# SCH_Eagle-Blinkyy_2025-12-08.net
KiCad netlist of a schematic drawn in EasyEDA
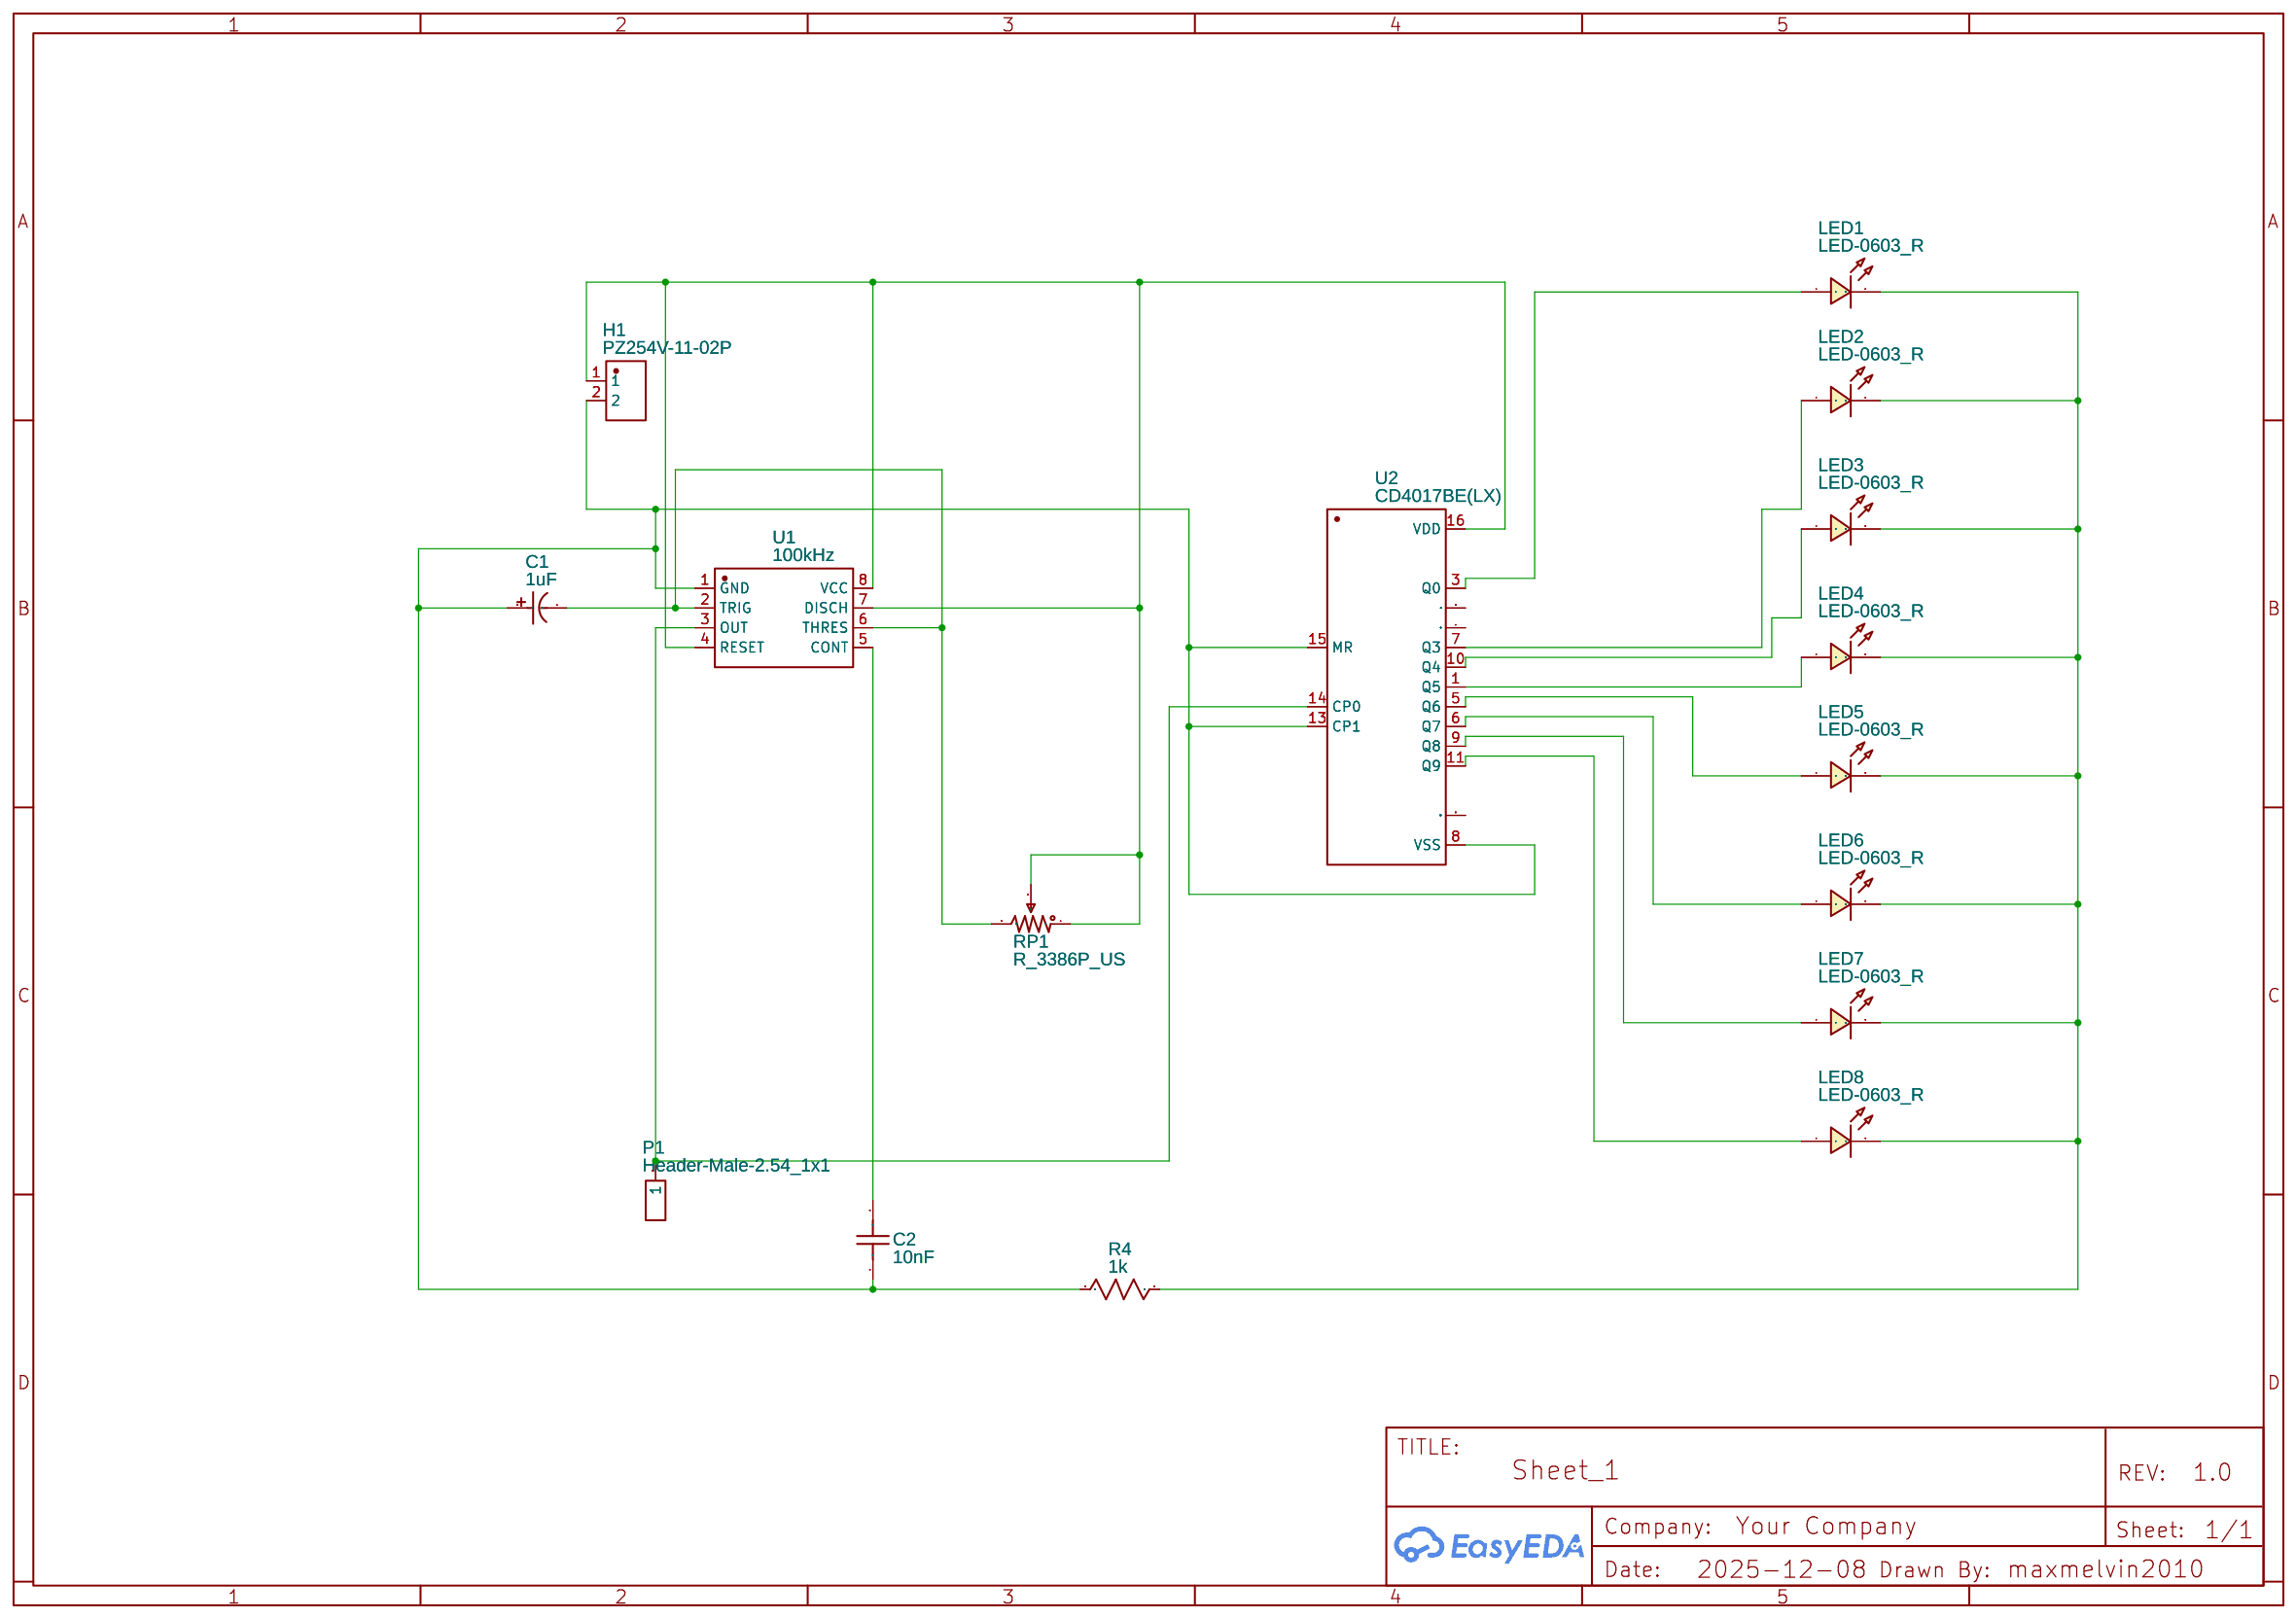
[diagram p0: schematic sheet]

(export (version "E")
  (design (tool "Eeschema 10.0.6"))
  (components
    (comp (ref "C1")
      (value "1uF")
      (fields (field (name "Manufacturer Part") "KF010M050C110A") (field (name "Manufacturer") "CapXon(丰宾)"))
      (libsource (lib "") (part "KF010M050C110A"))
    )
    (comp (ref "C2")
      (value "10nF")
      (fields (field (name "Manufacturer Part") "N09F1B103MN0B0S0N0") (field (name "Manufacturer") "STE(松田)"))
      (libsource (lib "") (part "N09F1B103MN0B0S0N0"))
    )
    (comp (ref "H1")
      (value "PZ254V-11-02P")
      (fields (field (name "Manufacturer") "XFCN(兴飞)"))
      (libsource (lib "") (part "PZ254V-11-02P"))
    )
    (comp (ref "LED1")
      (value "LED-0603_R")
      (fields
        (field (name "Manufacturer Part") "19-217/R6C-AL1M2VY/3T")
        (field (name "Manufacturer") "EVERLIGHT(台湾亿光)")
      )
      (libsource (lib "") (part "LED-0603_R"))
    )
    (comp (ref "LED2")
      (value "LED-0603_R")
      (fields
        (field (name "Manufacturer Part") "19-217/R6C-AL1M2VY/3T")
        (field (name "Manufacturer") "EVERLIGHT(台湾亿光)")
      )
      (libsource (lib "") (part "LED-0603_R"))
    )
    (comp (ref "LED3")
      (value "LED-0603_R")
      (fields
        (field (name "Manufacturer Part") "19-217/R6C-AL1M2VY/3T")
        (field (name "Manufacturer") "EVERLIGHT(台湾亿光)")
      )
      (libsource (lib "") (part "LED-0603_R"))
    )
    (comp (ref "LED4")
      (value "LED-0603_R")
      (fields
        (field (name "Manufacturer Part") "19-217/R6C-AL1M2VY/3T")
        (field (name "Manufacturer") "EVERLIGHT(台湾亿光)")
      )
      (libsource (lib "") (part "LED-0603_R"))
    )
    (comp (ref "LED5")
      (value "LED-0603_R")
      (fields
        (field (name "Manufacturer Part") "19-217/R6C-AL1M2VY/3T")
        (field (name "Manufacturer") "EVERLIGHT(台湾亿光)")
      )
      (libsource (lib "") (part "LED-0603_R"))
    )
    (comp (ref "LED6")
      (value "LED-0603_R")
      (fields
        (field (name "Manufacturer Part") "19-217/R6C-AL1M2VY/3T")
        (field (name "Manufacturer") "EVERLIGHT(台湾亿光)")
      )
      (libsource (lib "") (part "LED-0603_R"))
    )
    (comp (ref "LED7")
      (value "LED-0603_R")
      (fields
        (field (name "Manufacturer Part") "19-217/R6C-AL1M2VY/3T")
        (field (name "Manufacturer") "EVERLIGHT(台湾亿光)")
      )
      (libsource (lib "") (part "LED-0603_R"))
    )
    (comp (ref "LED8")
      (value "LED-0603_R")
      (fields
        (field (name "Manufacturer Part") "19-217/R6C-AL1M2VY/3T")
        (field (name "Manufacturer") "EVERLIGHT(台湾亿光)")
      )
      (libsource (lib "") (part "LED-0603_R"))
    )
    (comp (ref "P1")
      (value "Header-Male-2.54_1x1")
      (fields (field (name "Manufacturer Part") "2.54-1*1P针") (field (name "Manufacturer") "BOOMELE(博穆精密)"))
      (libsource (lib "") (part "Header-Male-2.54_1x1"))
    )
    (comp (ref "R4") (value "1k") (libsource (lib "") (part "R_1206_US")))
    (comp (ref "RP1") (value "R_3386P_US") (libsource (lib "") (part "R_3386P_US")))
    (comp (ref "U1")
      (value "100kHz")
      (fields (field (name "Manufacturer Part") "NE555P") (field (name "Manufacturer") "TI(德州仪器)"))
      (libsource (lib "") (part "NE555P"))
    )
    (comp (ref "U2")
      (value "CD4017BE(LX)")
      (fields (field (name "Manufacturer") "LX(灵星芯微)"))
      (libsource (lib "") (part "CD4017BE(LX)"))
    )
  )
  (nets
    (net (code "1") (name "Net-(LED1-Pad2)") (class "Default")
      (node (ref "LED1") (pin "2") (pinfunction "2_2") (pintype "unspecified"))
      (node (ref "LED2") (pin "2") (pinfunction "2_2") (pintype "unspecified"))
      (node (ref "LED3") (pin "2") (pinfunction "2_2") (pintype "unspecified"))
      (node (ref "LED4") (pin "2") (pinfunction "2_2") (pintype "unspecified"))
      (node (ref "LED5") (pin "2") (pinfunction "2_2") (pintype "unspecified"))
      (node (ref "LED6") (pin "2") (pinfunction "2_2") (pintype "unspecified"))
      (node (ref "LED7") (pin "2") (pinfunction "2_2") (pintype "unspecified"))
      (node (ref "LED8") (pin "2") (pinfunction "2_2") (pintype "unspecified"))
      (node (ref "R4") (pin "2") (pinfunction "2_2") (pintype "unspecified"))
    )
    (net (code "2") (name "Net-(U1-CONT)") (class "Default")
      (node (ref "C2") (pin "2") (pinfunction "2_2") (pintype "unspecified"))
      (node (ref "U1") (pin "5") (pinfunction "CONT_5") (pintype "unspecified"))
    )
    (net (code "3") (name "Net-(U1-DISCH)") (class "Default")
      (node (ref "H1") (pin "1") (pinfunction "1_1") (pintype "unspecified"))
      (node (ref "RP1") (pin "1") (pinfunction "1_1") (pintype "unspecified"))
      (node (ref "RP1") (pin "2") (pinfunction "2_2") (pintype "unspecified"))
      (node (ref "U1") (pin "4") (pinfunction "RESET_4") (pintype "unspecified"))
      (node (ref "U1") (pin "7") (pinfunction "DISCH_7") (pintype "unspecified"))
      (node (ref "U1") (pin "8") (pinfunction "VCC_8") (pintype "unspecified"))
      (node (ref "U2") (pin "16") (pinfunction "VDD_16") (pintype "unspecified"))
    )
    (net (code "4") (name "Net-(U1-GND)") (class "Default")
      (node (ref "C1") (pin "1") (pinfunction "1_1") (pintype "input"))
      (node (ref "C2") (pin "1") (pinfunction "1_1") (pintype "unspecified"))
      (node (ref "H1") (pin "2") (pinfunction "2_2") (pintype "unspecified"))
      (node (ref "R4") (pin "1") (pinfunction "1_1") (pintype "unspecified"))
      (node (ref "U1") (pin "1") (pinfunction "GND_1") (pintype "unspecified"))
      (node (ref "U2") (pin "13") (pinfunction "CP1_13") (pintype "unspecified"))
      (node (ref "U2") (pin "15") (pinfunction "MR_15") (pintype "unspecified"))
      (node (ref "U2") (pin "8") (pinfunction "VSS_8") (pintype "unspecified"))
    )
    (net (code "5") (name "Net-(U1-OUT)") (class "Default")
      (node (ref "P1") (pin "1") (pinfunction "1_1") (pintype "input"))
      (node (ref "U1") (pin "3") (pinfunction "OUT_3") (pintype "unspecified"))
      (node (ref "U2") (pin "14") (pinfunction "CP0_14") (pintype "unspecified"))
    )
    (net (code "6") (name "Net-(U1-THRES)") (class "Default")
      (node (ref "C1") (pin "2") (pinfunction "2_2") (pintype "input"))
      (node (ref "RP1") (pin "3") (pinfunction "3_3") (pintype "unspecified"))
      (node (ref "U1") (pin "2") (pinfunction "TRIG_2") (pintype "unspecified"))
      (node (ref "U1") (pin "6") (pinfunction "THRES_6") (pintype "unspecified"))
    )
    (net (code "7") (name "Net-(U2-Q0)") (class "Default")
      (node (ref "LED1") (pin "1") (pinfunction "1_1") (pintype "unspecified"))
      (node (ref "U2") (pin "3") (pinfunction "Q0_3") (pintype "unspecified"))
    )
    (net (code "8") (name "Net-(U2-Q3)") (class "Default")
      (node (ref "LED2") (pin "1") (pinfunction "1_1") (pintype "unspecified"))
      (node (ref "U2") (pin "7") (pinfunction "Q3_7") (pintype "unspecified"))
    )
    (net (code "9") (name "Net-(U2-Q4)") (class "Default")
      (node (ref "LED3") (pin "1") (pinfunction "1_1") (pintype "unspecified"))
      (node (ref "U2") (pin "10") (pinfunction "Q4_10") (pintype "unspecified"))
    )
    (net (code "10") (name "Net-(U2-Q5)") (class "Default")
      (node (ref "LED4") (pin "1") (pinfunction "1_1") (pintype "unspecified"))
      (node (ref "U2") (pin "1") (pinfunction "Q5_1") (pintype "unspecified"))
    )
    (net (code "11") (name "Net-(U2-Q6)") (class "Default")
      (node (ref "LED5") (pin "1") (pinfunction "1_1") (pintype "unspecified"))
      (node (ref "U2") (pin "5") (pinfunction "Q6_5") (pintype "unspecified"))
    )
    (net (code "12") (name "Net-(U2-Q7)") (class "Default")
      (node (ref "LED6") (pin "1") (pinfunction "1_1") (pintype "unspecified"))
      (node (ref "U2") (pin "6") (pinfunction "Q7_6") (pintype "unspecified"))
    )
    (net (code "13") (name "Net-(U2-Q8)") (class "Default")
      (node (ref "LED7") (pin "1") (pinfunction "1_1") (pintype "unspecified"))
      (node (ref "U2") (pin "9") (pinfunction "Q8_9") (pintype "unspecified"))
    )
    (net (code "14") (name "Net-(U2-Q9)") (class "Default")
      (node (ref "LED8") (pin "1") (pinfunction "1_1") (pintype "unspecified"))
      (node (ref "U2") (pin "11") (pinfunction "Q9_11") (pintype "unspecified"))
    )
    (net (code "15") (name "unconnected-(U2-Q1-Pad2)") (class "Default")
      (node (ref "U2") (pin "2") (pinfunction "Q1_2") (pintype "unspecified"))
    )
    (net (code "16") (name "unconnected-(U2-Q2-Pad4)") (class "Default")
      (node (ref "U2") (pin "4") (pinfunction "Q2_4") (pintype "unspecified"))
    )
    (net (code "17") (name "unconnected-(U2-Q5-9-Pad12)") (class "Default")
      (node (ref "U2") (pin "12") (pinfunction "Q5-9_12") (pintype "unspecified"))
    )
  )
)
